# AX-12_PSU.net
KiCad netlist of a schematic drawn in Altium Designer
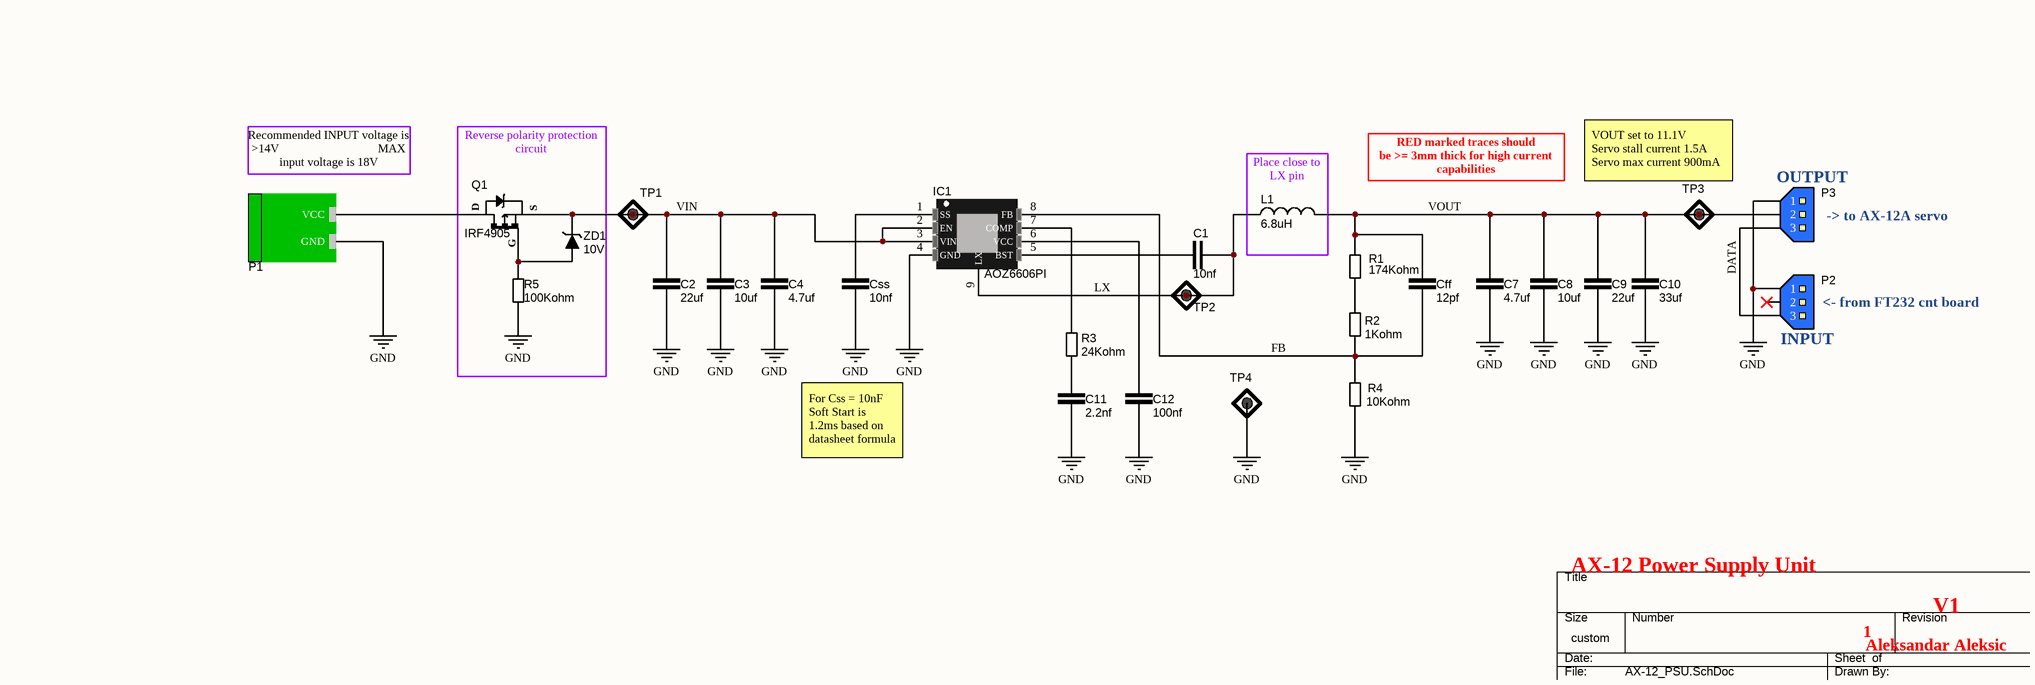
[diagram p0: AX-12_PSU.SchDoc]

(export (version "E")
  (design (tool "Eeschema 10.0.6"))
  (components
    (comp (ref "C1")
      (value "10nf")
      (footprint "CAP_0603")
      (description "CAP CER 10nF 0603 25V X7R")
      (libsource (lib "CapacitorsIntegrated") (part "0000005"))
    )
    (comp (ref "C2")
      (value "22uf")
      (footprint "CAP_0805")
      (description "CAP CER 22uF 0805 25V X5R")
      (libsource (lib "CapacitorsIntegrated") (part "0000001"))
    )
    (comp (ref "C3")
      (value "10uf")
      (footprint "CAP_0805")
      (description "CAP CER 10uF 0805 25V X5R")
      (libsource (lib "CapacitorsIntegrated") (part "0000002"))
    )
    (comp (ref "C4")
      (value "4.7uf")
      (footprint "CAP_0805")
      (description "CAP CER 4.7uF 0805 25V X5R")
      (libsource (lib "CapacitorsIntegrated") (part "0000003"))
    )
    (comp (ref "C7")
      (value "4.7uf")
      (footprint "CAP_0805")
      (description "CAP CER 4.7uF 0805 25V X5R")
      (libsource (lib "CapacitorsIntegrated") (part "0000003"))
    )
    (comp (ref "C8")
      (value "10uf")
      (footprint "CAP_0805")
      (description "CAP CER 10uF 0805 25V X5R")
      (libsource (lib "CapacitorsIntegrated") (part "0000002"))
    )
    (comp (ref "C9")
      (value "22uf")
      (footprint "CAP_0805")
      (description "CAP CER 22uF 0805 25V X5R")
      (libsource (lib "CapacitorsIntegrated") (part "0000001"))
    )
    (comp (ref "C10")
      (value "33uf")
      (footprint "CAP_1206")
      (description "CAP CER 33uF 1206 25V X5R")
      (libsource (lib "CapacitorsIntegrated") (part "0000004"))
    )
    (comp (ref "C11")
      (value "2.2nf")
      (footprint "CAP_0603")
      (description "CAP CER 2.2nF 0603 25V X7R")
      (libsource (lib "CapacitorsIntegrated") (part "0000006"))
    )
    (comp (ref "C12")
      (value "100nf")
      (footprint "CAP_0603")
      (description "CAP CER 100nF 0603 25V X7R")
      (libsource (lib "CapacitorsIntegrated") (part "0000007"))
    )
    (comp (ref "Cff")
      (value "12pf")
      (footprint "CAP_0603")
      (description "CAP CER 12pF 0603 25V X7R")
      (libsource (lib "CapacitorsIntegrated") (part "0000008"))
    )
    (comp (ref "Css")
      (value "10nf")
      (footprint "CAP_0603")
      (description "CAP CER 10nF 0603 25V X7R")
      (libsource (lib "") (part "0000005_1"))
    )
    (comp (ref "IC1")
      (value "AOZ6606PI")
      (footprint "SOP127P600X170_HS-9N")
      (libsource (lib "IntegratedCircuits") (part "AOZ6606PI"))
    )
    (comp (ref "L1")
      (value "6.8uH")
      (footprint "INDM108103X40N")
      (description "IND 6.8uH 8A 23.3mOHM 13.5A ISAT")
      (libsource (lib "InductorIntegrated") (part "L000002"))
    )
    (comp (ref "P1")
      (value "2EDGRC-5.08-02P-14-00A(H)")
      (footprint "PWR_Con")
      (description "TERM BLOCK HDR 2POS 90DEG 5.08MM")
      (libsource (lib "Electro_Mechanical") (part "00000002"))
    )
    (comp (ref "P2")
      (value "TE CONNECTIVITY_3PIN_MALE")
      (footprint "TE CONNECTIVITY_3PIN_MALE")
      (description "BLUE_3PIN_CONECTOR")
      (fields (field (name "MANUFACTURER") "TE CONNECTIVITY / AMP"))
      (libsource (lib "Electro_Mechanical") (part "TE CONNECTIVITY_3PIN_MALE"))
    )
    (comp (ref "P3")
      (value "TE CONNECTIVITY_3PIN_MALE")
      (footprint "TE CONNECTIVITY_3PIN_MALE")
      (description "BLUE_3PIN_CONECTOR")
      (fields (field (name "MANUFACTURER") "TE CONNECTIVITY / AMP"))
      (libsource (lib "Electro_Mechanical") (part "TE CONNECTIVITY_3PIN_MALE"))
    )
    (comp (ref "Q1")
      (value "IRF4905")
      (footprint "DPAK254P1524X483-3N")
      (fields
        (field (name "MANUFACTURER") "International Rectifier")
        (field (name "MANUFACTURER PART NUMBER") "IRF1404ZSPBF")
      )
      (libsource (lib "IntegratedCircuits") (part "IRF4905"))
    )
    (comp (ref "R1")
      (value "174Kohm")
      (footprint "RES_0603")
      (description "RES 174K OHM 1% 1/10W 0603")
      (libsource (lib "ResistorsIntegrated") (part "R000003"))
    )
    (comp (ref "R2")
      (value "1Kohm")
      (footprint "RES_0603")
      (description "RES 1K OHM 1% 1/10W 0603")
      (libsource (lib "ResistorsIntegrated") (part "R000004"))
    )
    (comp (ref "R3")
      (value "24Kohm")
      (footprint "RES_0603")
      (description "RES 24K OHM 1% 1/10W 0603")
      (libsource (lib "ResistorsIntegrated") (part "R000005"))
    )
    (comp (ref "R4")
      (value "10Kohm")
      (footprint "RES_0603")
      (description "RES 10K OHM 1% 1/10W 0603")
      (libsource (lib "ResistorsIntegrated") (part "R000001"))
    )
    (comp (ref "R5")
      (value "100Kohm")
      (footprint "RES_0603")
      (description "RES 100K OHM 1% 1/10W 0603")
      (libsource (lib "ResistorsIntegrated") (part "R000006"))
    )
    (comp (ref "TP1")
      (value "TestPoint")
      (footprint "TestPoint")
      (libsource (lib "IntegratedCircuits") (part "TP001"))
    )
    (comp (ref "TP2")
      (value "TestPoint")
      (footprint "TestPoint")
      (libsource (lib "IntegratedCircuits") (part "TP001"))
    )
    (comp (ref "TP3")
      (value "TestPoint")
      (footprint "TestPoint")
      (libsource (lib "IntegratedCircuits") (part "TP001"))
    )
    (comp (ref "TP4")
      (value "TestPoint")
      (footprint "TestPoint")
      (libsource (lib "IntegratedCircuits") (part "TP001"))
    )
    (comp (ref "ZD1")
      (value "10V")
      (footprint "DIO_SMA")
      (description "Zener Diode 10 V 5 W ±5% Surface Mount SMC (DO-214AB)")
      (libsource (lib "IntegratedCircuits") (part "1SMA5931-AU_R1"))
    )
  )
  (nets
    (net (code "1") (name "/DATA") (class "Default")
      (node (ref "P2") (pin "3") (pinfunction "3_3") (pintype "passive"))
      (node (ref "P3") (pin "3") (pinfunction "3_3") (pintype "passive"))
    )
    (net (code "2") (name "/FB") (class "Default")
      (node (ref "Cff") (pin "1") (pinfunction "1_1") (pintype "passive"))
      (node (ref "IC1") (pin "8") (pinfunction "FB_8") (pintype "passive"))
      (node (ref "R2") (pin "1") (pinfunction "1_1") (pintype "passive"))
      (node (ref "R4") (pin "2") (pinfunction "2_2") (pintype "passive"))
    )
    (net (code "3") (name "/LX") (class "Default")
      (node (ref "C1") (pin "2") (pinfunction "2_2") (pintype "passive"))
      (node (ref "IC1") (pin "9") (pinfunction "LX_9") (pintype "passive"))
      (node (ref "L1") (pin "1") (pinfunction "1_1") (pintype "passive"))
      (node (ref "TP2") (pin "1") (pinfunction "1_1") (pintype "passive"))
    )
    (net (code "4") (name "/VIN") (class "Default")
      (node (ref "C2") (pin "2") (pinfunction "2_2") (pintype "passive"))
      (node (ref "C3") (pin "2") (pinfunction "2_2") (pintype "passive"))
      (node (ref "C4") (pin "2") (pinfunction "2_2") (pintype "passive"))
      (node (ref "IC1") (pin "2") (pinfunction "EN_2") (pintype "passive"))
      (node (ref "IC1") (pin "3") (pinfunction "VIN_3") (pintype "passive"))
      (node (ref "Q1") (pin "3") (pinfunction "3_3") (pintype "passive"))
      (node (ref "TP1") (pin "1") (pinfunction "1_1") (pintype "passive"))
      (node (ref "ZD1") (pin "1") (pinfunction "Cathode_1") (pintype "passive"))
    )
    (net (code "5") (name "/VOUT") (class "Default")
      (node (ref "C10") (pin "2") (pinfunction "2_2") (pintype "passive"))
      (node (ref "C7") (pin "2") (pinfunction "2_2") (pintype "passive"))
      (node (ref "C8") (pin "2") (pinfunction "2_2") (pintype "passive"))
      (node (ref "C9") (pin "2") (pinfunction "2_2") (pintype "passive"))
      (node (ref "Cff") (pin "2") (pinfunction "2_2") (pintype "passive"))
      (node (ref "L1") (pin "2") (pinfunction "2_2") (pintype "passive"))
      (node (ref "P3") (pin "2") (pinfunction "2_2") (pintype "passive"))
      (node (ref "R1") (pin "2") (pinfunction "2_2") (pintype "passive"))
      (node (ref "TP3") (pin "1") (pinfunction "1_1") (pintype "passive"))
    )
    (net (code "6") (name "GND") (class "Default")
      (node (ref "C10") (pin "1") (pinfunction "1_1") (pintype "passive"))
      (node (ref "C11") (pin "1") (pinfunction "1_1") (pintype "passive"))
      (node (ref "C12") (pin "1") (pinfunction "1_1") (pintype "passive"))
      (node (ref "C2") (pin "1") (pinfunction "1_1") (pintype "passive"))
      (node (ref "C3") (pin "1") (pinfunction "1_1") (pintype "passive"))
      (node (ref "C4") (pin "1") (pinfunction "1_1") (pintype "passive"))
      (node (ref "C7") (pin "1") (pinfunction "1_1") (pintype "passive"))
      (node (ref "C8") (pin "1") (pinfunction "1_1") (pintype "passive"))
      (node (ref "C9") (pin "1") (pinfunction "1_1") (pintype "passive"))
      (node (ref "Css") (pin "1") (pinfunction "1_1") (pintype "passive"))
      (node (ref "IC1") (pin "4") (pinfunction "GND_4") (pintype "passive"))
      (node (ref "P1") (pin "1") (pinfunction "GND_1") (pintype "passive"))
      (node (ref "P2") (pin "1") (pinfunction "1_1") (pintype "passive"))
      (node (ref "P3") (pin "1") (pinfunction "1_1") (pintype "passive"))
      (node (ref "R4") (pin "1") (pinfunction "1_1") (pintype "passive"))
      (node (ref "R5") (pin "1") (pinfunction "1_1") (pintype "passive"))
      (node (ref "TP4") (pin "1") (pinfunction "1_1") (pintype "passive"))
    )
    (net (code "7") (name "Net-(C11-Pad2)") (class "Default")
      (node (ref "C11") (pin "2") (pinfunction "2_2") (pintype "passive"))
      (node (ref "R3") (pin "1") (pinfunction "1_1") (pintype "passive"))
    )
    (net (code "8") (name "Net-(IC1-BST)") (class "Default")
      (node (ref "C1") (pin "1") (pinfunction "1_1") (pintype "passive"))
      (node (ref "IC1") (pin "5") (pinfunction "BST_5") (pintype "passive"))
    )
    (net (code "9") (name "Net-(IC1-COMP)") (class "Default")
      (node (ref "IC1") (pin "7") (pinfunction "COMP_7") (pintype "passive"))
      (node (ref "R3") (pin "2") (pinfunction "2_2") (pintype "passive"))
    )
    (net (code "10") (name "Net-(IC1-SS)") (class "Default")
      (node (ref "Css") (pin "2") (pinfunction "2_2") (pintype "passive"))
      (node (ref "IC1") (pin "1") (pinfunction "SS_1") (pintype "passive"))
    )
    (net (code "11") (name "Net-(IC1-VCC)") (class "Default")
      (node (ref "C12") (pin "2") (pinfunction "2_2") (pintype "passive"))
      (node (ref "IC1") (pin "6") (pinfunction "VCC_6") (pintype "passive"))
    )
    (net (code "12") (name "Net-(P1-VCC)") (class "Default")
      (node (ref "P1") (pin "2") (pinfunction "VCC_2") (pintype "passive"))
      (node (ref "Q1") (pin "4") (pinfunction "4_4") (pintype "passive"))
    )
    (net (code "13") (name "Net-(Q1-G)") (class "Default")
      (node (ref "Q1") (pin "1") (pinfunction "G_1") (pintype "passive"))
      (node (ref "R5") (pin "2") (pinfunction "2_2") (pintype "passive"))
      (node (ref "ZD1") (pin "2") (pinfunction "Anode_2") (pintype "passive"))
    )
    (net (code "14") (name "Net-(R1-Pad1)") (class "Default")
      (node (ref "R1") (pin "1") (pinfunction "1_1") (pintype "passive"))
      (node (ref "R2") (pin "2") (pinfunction "2_2") (pintype "passive"))
    )
    (net (code "15") (name "unconnected-(P2-Pad2)") (class "Default")
      (node (ref "P2") (pin "2") (pinfunction "2_2") (pintype "passive+no_connect"))
    )
  )
)
